# STEERING_WHEEL_SWITCHES_V2_SWITCH_BOARD.net
KiCad netlist of a schematic drawn in Altium Designer
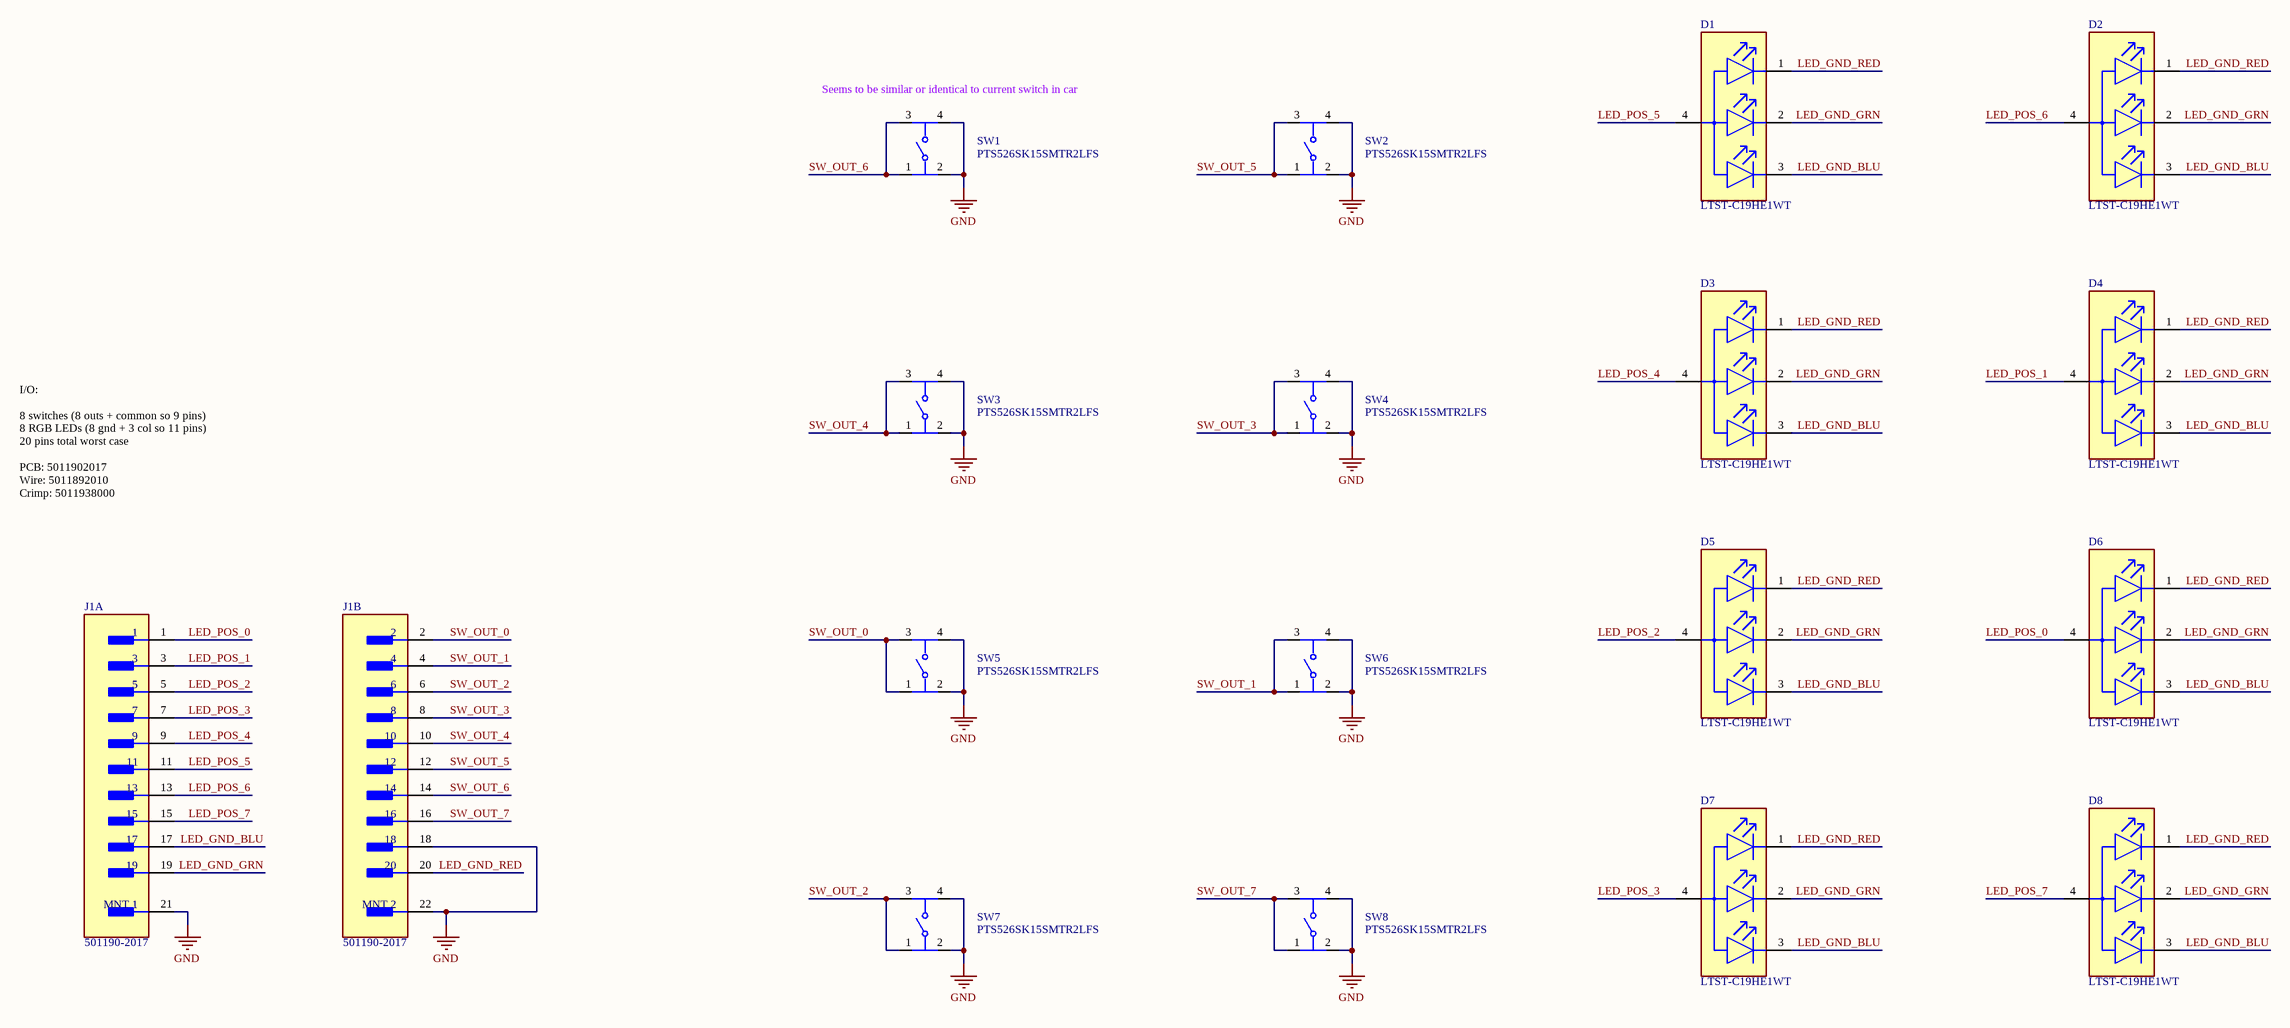
[diagram p0: STEERING_WHEEL_SWITCHES_V2_SWITCH_BOARD.SchDoc]

(export (version "E")
  (design (tool "Eeschema 10.0.6"))
  (components
    (comp (ref "D1")
      (value "LTST-C19HE1WT")
      (footprint "FP-LTST-C19HE1WT-MFG")
      (description "LED RGB DIFFUSED CHIP SMD")
      (libsource (lib "Altium Content Vault") (part "2c4e1fdd461916b293eda504ca5a2b6"))
    )
    (comp (ref "D2")
      (value "LTST-C19HE1WT")
      (footprint "FP-LTST-C19HE1WT-MFG")
      (description "LED RGB DIFFUSED CHIP SMD")
      (libsource (lib "Altium Content Vault") (part "2c4e1fdd461916b293eda504ca5a2b6"))
    )
    (comp (ref "D3")
      (value "LTST-C19HE1WT")
      (footprint "FP-LTST-C19HE1WT-MFG")
      (description "LED RGB DIFFUSED CHIP SMD")
      (libsource (lib "Altium Content Vault") (part "2c4e1fdd461916b293eda504ca5a2b6"))
    )
    (comp (ref "D4")
      (value "LTST-C19HE1WT")
      (footprint "FP-LTST-C19HE1WT-MFG")
      (description "LED RGB DIFFUSED CHIP SMD")
      (libsource (lib "Altium Content Vault") (part "2c4e1fdd461916b293eda504ca5a2b6"))
    )
    (comp (ref "D5")
      (value "LTST-C19HE1WT")
      (footprint "FP-LTST-C19HE1WT-MFG")
      (description "LED RGB DIFFUSED CHIP SMD")
      (libsource (lib "Altium Content Vault") (part "2c4e1fdd461916b293eda504ca5a2b6"))
    )
    (comp (ref "D6")
      (value "LTST-C19HE1WT")
      (footprint "FP-LTST-C19HE1WT-MFG")
      (description "LED RGB DIFFUSED CHIP SMD")
      (libsource (lib "Altium Content Vault") (part "2c4e1fdd461916b293eda504ca5a2b6"))
    )
    (comp (ref "D7")
      (value "LTST-C19HE1WT")
      (footprint "FP-LTST-C19HE1WT-MFG")
      (description "LED RGB DIFFUSED CHIP SMD")
      (libsource (lib "Altium Content Vault") (part "2c4e1fdd461916b293eda504ca5a2b6"))
    )
    (comp (ref "D8")
      (value "LTST-C19HE1WT")
      (footprint "FP-LTST-C19HE1WT-MFG")
      (description "LED RGB DIFFUSED CHIP SMD")
      (libsource (lib "Altium Content Vault") (part "2c4e1fdd461916b293eda504ca5a2b6"))
    )
    (comp (ref "J1")
      (value "501190-2017")
      (footprint "FP-501190-2017-MFG")
      (description "CONN HEADER SMD 20POS 1MM")
      (libsource (lib "Altium Content Vault") (part "3088fde206a7053fe950ea66454f304"))
    )
    (comp (ref "SW1")
      (value "PTS526SK15SMTR2LFS")
      (footprint "FP-PTS526SK15SMTR2LFS-MFG")
      (description "TACT 5.2 X 5.2, 1.5 MM H, 260GF,")
      (fields
        (field (name "MANUFACTURER") "C&K")
        (field (name "OCTOPART") "https://octopart.com/pts526+sk15+smtr2+lfs-c%26k+components-100617999")
      )
      (libsource (lib "Altium Content Vault") (part "b8895f3f4cefb76e1819d2863dba89b"))
    )
    (comp (ref "SW2")
      (value "PTS526SK15SMTR2LFS")
      (footprint "FP-PTS526SK15SMTR2LFS-MFG")
      (description "TACT 5.2 X 5.2, 1.5 MM H, 260GF,")
      (fields
        (field (name "MANUFACTURER") "C&K")
        (field (name "OCTOPART") "https://octopart.com/pts526+sk15+smtr2+lfs-c%26k+components-100617999")
      )
      (libsource (lib "Altium Content Vault") (part "b8895f3f4cefb76e1819d2863dba89b"))
    )
    (comp (ref "SW3")
      (value "PTS526SK15SMTR2LFS")
      (footprint "FP-PTS526SK15SMTR2LFS-MFG")
      (description "TACT 5.2 X 5.2, 1.5 MM H, 260GF,")
      (fields
        (field (name "MANUFACTURER") "C&K")
        (field (name "OCTOPART") "https://octopart.com/pts526+sk15+smtr2+lfs-c%26k+components-100617999")
      )
      (libsource (lib "Altium Content Vault") (part "b8895f3f4cefb76e1819d2863dba89b"))
    )
    (comp (ref "SW4")
      (value "PTS526SK15SMTR2LFS")
      (footprint "FP-PTS526SK15SMTR2LFS-MFG")
      (description "TACT 5.2 X 5.2, 1.5 MM H, 260GF,")
      (fields
        (field (name "MANUFACTURER") "C&K")
        (field (name "OCTOPART") "https://octopart.com/pts526+sk15+smtr2+lfs-c%26k+components-100617999")
      )
      (libsource (lib "Altium Content Vault") (part "b8895f3f4cefb76e1819d2863dba89b"))
    )
    (comp (ref "SW5")
      (value "PTS526SK15SMTR2LFS")
      (footprint "FP-PTS526SK15SMTR2LFS-MFG")
      (description "TACT 5.2 X 5.2, 1.5 MM H, 260GF,")
      (fields
        (field (name "MANUFACTURER") "C&K")
        (field (name "OCTOPART") "https://octopart.com/pts526+sk15+smtr2+lfs-c%26k+components-100617999")
      )
      (libsource (lib "Altium Content Vault") (part "b8895f3f4cefb76e1819d2863dba89b"))
    )
    (comp (ref "SW6")
      (value "PTS526SK15SMTR2LFS")
      (footprint "FP-PTS526SK15SMTR2LFS-MFG")
      (description "TACT 5.2 X 5.2, 1.5 MM H, 260GF,")
      (fields
        (field (name "MANUFACTURER") "C&K")
        (field (name "OCTOPART") "https://octopart.com/pts526+sk15+smtr2+lfs-c%26k+components-100617999")
      )
      (libsource (lib "Altium Content Vault") (part "b8895f3f4cefb76e1819d2863dba89b"))
    )
    (comp (ref "SW7")
      (value "PTS526SK15SMTR2LFS")
      (footprint "FP-PTS526SK15SMTR2LFS-MFG")
      (description "TACT 5.2 X 5.2, 1.5 MM H, 260GF,")
      (fields
        (field (name "MANUFACTURER") "C&K")
        (field (name "OCTOPART") "https://octopart.com/pts526+sk15+smtr2+lfs-c%26k+components-100617999")
      )
      (libsource (lib "Altium Content Vault") (part "b8895f3f4cefb76e1819d2863dba89b"))
    )
    (comp (ref "SW8")
      (value "PTS526SK15SMTR2LFS")
      (footprint "FP-PTS526SK15SMTR2LFS-MFG")
      (description "TACT 5.2 X 5.2, 1.5 MM H, 260GF,")
      (fields
        (field (name "MANUFACTURER") "C&K")
        (field (name "OCTOPART") "https://octopart.com/pts526+sk15+smtr2+lfs-c%26k+components-100617999")
      )
      (libsource (lib "Altium Content Vault") (part "b8895f3f4cefb76e1819d2863dba89b"))
    )
  )
  (nets
    (net (code "1") (name "/LED_GND_BLU") (class "Default")
      (node (ref "D1") (pin "3") (pinfunction "BLUE_C_3") (pintype "passive"))
      (node (ref "D2") (pin "3") (pinfunction "BLUE_C_3") (pintype "passive"))
      (node (ref "D3") (pin "3") (pinfunction "BLUE_C_3") (pintype "passive"))
      (node (ref "D4") (pin "3") (pinfunction "BLUE_C_3") (pintype "passive"))
      (node (ref "D5") (pin "3") (pinfunction "BLUE_C_3") (pintype "passive"))
      (node (ref "D6") (pin "3") (pinfunction "BLUE_C_3") (pintype "passive"))
      (node (ref "D7") (pin "3") (pinfunction "BLUE_C_3") (pintype "passive"))
      (node (ref "D8") (pin "3") (pinfunction "BLUE_C_3") (pintype "passive"))
      (node (ref "J1") (pin "17") (pinfunction "17_17") (pintype "passive"))
    )
    (net (code "2") (name "/LED_GND_GRN") (class "Default")
      (node (ref "D1") (pin "2") (pinfunction "GREEN_C_2") (pintype "passive"))
      (node (ref "D2") (pin "2") (pinfunction "GREEN_C_2") (pintype "passive"))
      (node (ref "D3") (pin "2") (pinfunction "GREEN_C_2") (pintype "passive"))
      (node (ref "D4") (pin "2") (pinfunction "GREEN_C_2") (pintype "passive"))
      (node (ref "D5") (pin "2") (pinfunction "GREEN_C_2") (pintype "passive"))
      (node (ref "D6") (pin "2") (pinfunction "GREEN_C_2") (pintype "passive"))
      (node (ref "D7") (pin "2") (pinfunction "GREEN_C_2") (pintype "passive"))
      (node (ref "D8") (pin "2") (pinfunction "GREEN_C_2") (pintype "passive"))
      (node (ref "J1") (pin "19") (pinfunction "19_19") (pintype "passive"))
    )
    (net (code "3") (name "/LED_GND_RED") (class "Default")
      (node (ref "D1") (pin "1") (pinfunction "RED_C_1") (pintype "passive"))
      (node (ref "D2") (pin "1") (pinfunction "RED_C_1") (pintype "passive"))
      (node (ref "D3") (pin "1") (pinfunction "RED_C_1") (pintype "passive"))
      (node (ref "D4") (pin "1") (pinfunction "RED_C_1") (pintype "passive"))
      (node (ref "D5") (pin "1") (pinfunction "RED_C_1") (pintype "passive"))
      (node (ref "D6") (pin "1") (pinfunction "RED_C_1") (pintype "passive"))
      (node (ref "D7") (pin "1") (pinfunction "RED_C_1") (pintype "passive"))
      (node (ref "D8") (pin "1") (pinfunction "RED_C_1") (pintype "passive"))
      (node (ref "J1") (pin "20") (pinfunction "20_20") (pintype "passive"))
    )
    (net (code "4") (name "/LED_POS_0") (class "Default")
      (node (ref "D6") (pin "4") (pinfunction "A_4") (pintype "passive"))
      (node (ref "J1") (pin "1") (pinfunction "1_1") (pintype "passive"))
    )
    (net (code "5") (name "/LED_POS_1") (class "Default")
      (node (ref "D4") (pin "4") (pinfunction "A_4") (pintype "passive"))
      (node (ref "J1") (pin "3") (pinfunction "3_3") (pintype "passive"))
    )
    (net (code "6") (name "/LED_POS_2") (class "Default")
      (node (ref "D5") (pin "4") (pinfunction "A_4") (pintype "passive"))
      (node (ref "J1") (pin "5") (pinfunction "5_5") (pintype "passive"))
    )
    (net (code "7") (name "/LED_POS_3") (class "Default")
      (node (ref "D7") (pin "4") (pinfunction "A_4") (pintype "passive"))
      (node (ref "J1") (pin "7") (pinfunction "7_7") (pintype "passive"))
    )
    (net (code "8") (name "/LED_POS_4") (class "Default")
      (node (ref "D3") (pin "4") (pinfunction "A_4") (pintype "passive"))
      (node (ref "J1") (pin "9") (pinfunction "9_9") (pintype "passive"))
    )
    (net (code "9") (name "/LED_POS_5") (class "Default")
      (node (ref "D1") (pin "4") (pinfunction "A_4") (pintype "passive"))
      (node (ref "J1") (pin "11") (pinfunction "11_11") (pintype "passive"))
    )
    (net (code "10") (name "/LED_POS_6") (class "Default")
      (node (ref "D2") (pin "4") (pinfunction "A_4") (pintype "passive"))
      (node (ref "J1") (pin "13") (pinfunction "13_13") (pintype "passive"))
    )
    (net (code "11") (name "/LED_POS_7") (class "Default")
      (node (ref "D8") (pin "4") (pinfunction "A_4") (pintype "passive"))
      (node (ref "J1") (pin "15") (pinfunction "15_15") (pintype "passive"))
    )
    (net (code "12") (name "/SW_OUT_0") (class "Default")
      (node (ref "J1") (pin "2") (pinfunction "2_2") (pintype "passive"))
      (node (ref "SW5") (pin "1") (pinfunction "1_1") (pintype "passive"))
      (node (ref "SW5") (pin "3") (pinfunction "3_3") (pintype "passive"))
    )
    (net (code "13") (name "/SW_OUT_1") (class "Default")
      (node (ref "J1") (pin "4") (pinfunction "4_4") (pintype "passive"))
      (node (ref "SW6") (pin "1") (pinfunction "1_1") (pintype "passive"))
      (node (ref "SW6") (pin "3") (pinfunction "3_3") (pintype "passive"))
    )
    (net (code "14") (name "/SW_OUT_2") (class "Default")
      (node (ref "J1") (pin "6") (pinfunction "6_6") (pintype "passive"))
      (node (ref "SW7") (pin "1") (pinfunction "1_1") (pintype "passive"))
      (node (ref "SW7") (pin "3") (pinfunction "3_3") (pintype "passive"))
    )
    (net (code "15") (name "/SW_OUT_3") (class "Default")
      (node (ref "J1") (pin "8") (pinfunction "8_8") (pintype "passive"))
      (node (ref "SW4") (pin "1") (pinfunction "1_1") (pintype "passive"))
      (node (ref "SW4") (pin "3") (pinfunction "3_3") (pintype "passive"))
    )
    (net (code "16") (name "/SW_OUT_4") (class "Default")
      (node (ref "J1") (pin "10") (pinfunction "10_10") (pintype "passive"))
      (node (ref "SW3") (pin "1") (pinfunction "1_1") (pintype "passive"))
      (node (ref "SW3") (pin "3") (pinfunction "3_3") (pintype "passive"))
    )
    (net (code "17") (name "/SW_OUT_5") (class "Default")
      (node (ref "J1") (pin "12") (pinfunction "12_12") (pintype "passive"))
      (node (ref "SW2") (pin "1") (pinfunction "1_1") (pintype "passive"))
      (node (ref "SW2") (pin "3") (pinfunction "3_3") (pintype "passive"))
    )
    (net (code "18") (name "/SW_OUT_6") (class "Default")
      (node (ref "J1") (pin "14") (pinfunction "14_14") (pintype "passive"))
      (node (ref "SW1") (pin "1") (pinfunction "1_1") (pintype "passive"))
      (node (ref "SW1") (pin "3") (pinfunction "3_3") (pintype "passive"))
    )
    (net (code "19") (name "/SW_OUT_7") (class "Default")
      (node (ref "J1") (pin "16") (pinfunction "16_16") (pintype "passive"))
      (node (ref "SW8") (pin "1") (pinfunction "1_1") (pintype "passive"))
      (node (ref "SW8") (pin "3") (pinfunction "3_3") (pintype "passive"))
    )
    (net (code "20") (name "GND") (class "Default")
      (node (ref "J1") (pin "18") (pinfunction "18_18") (pintype "passive"))
      (node (ref "J1") (pin "21") (pinfunction "MNT_1_21") (pintype "passive"))
      (node (ref "J1") (pin "22") (pinfunction "MNT_2_22") (pintype "passive"))
      (node (ref "SW1") (pin "2") (pinfunction "2_2") (pintype "passive"))
      (node (ref "SW1") (pin "4") (pinfunction "4_4") (pintype "passive"))
      (node (ref "SW2") (pin "2") (pinfunction "2_2") (pintype "passive"))
      (node (ref "SW2") (pin "4") (pinfunction "4_4") (pintype "passive"))
      (node (ref "SW3") (pin "2") (pinfunction "2_2") (pintype "passive"))
      (node (ref "SW3") (pin "4") (pinfunction "4_4") (pintype "passive"))
      (node (ref "SW4") (pin "2") (pinfunction "2_2") (pintype "passive"))
      (node (ref "SW4") (pin "4") (pinfunction "4_4") (pintype "passive"))
      (node (ref "SW5") (pin "2") (pinfunction "2_2") (pintype "passive"))
      (node (ref "SW5") (pin "4") (pinfunction "4_4") (pintype "passive"))
      (node (ref "SW6") (pin "2") (pinfunction "2_2") (pintype "passive"))
      (node (ref "SW6") (pin "4") (pinfunction "4_4") (pintype "passive"))
      (node (ref "SW7") (pin "2") (pinfunction "2_2") (pintype "passive"))
      (node (ref "SW7") (pin "4") (pinfunction "4_4") (pintype "passive"))
      (node (ref "SW8") (pin "2") (pinfunction "2_2") (pintype "passive"))
      (node (ref "SW8") (pin "4") (pinfunction "4_4") (pintype "passive"))
    )
  )
)
